# PowerConversion60-12.net
KiCad netlist of a schematic drawn in Altium Designer
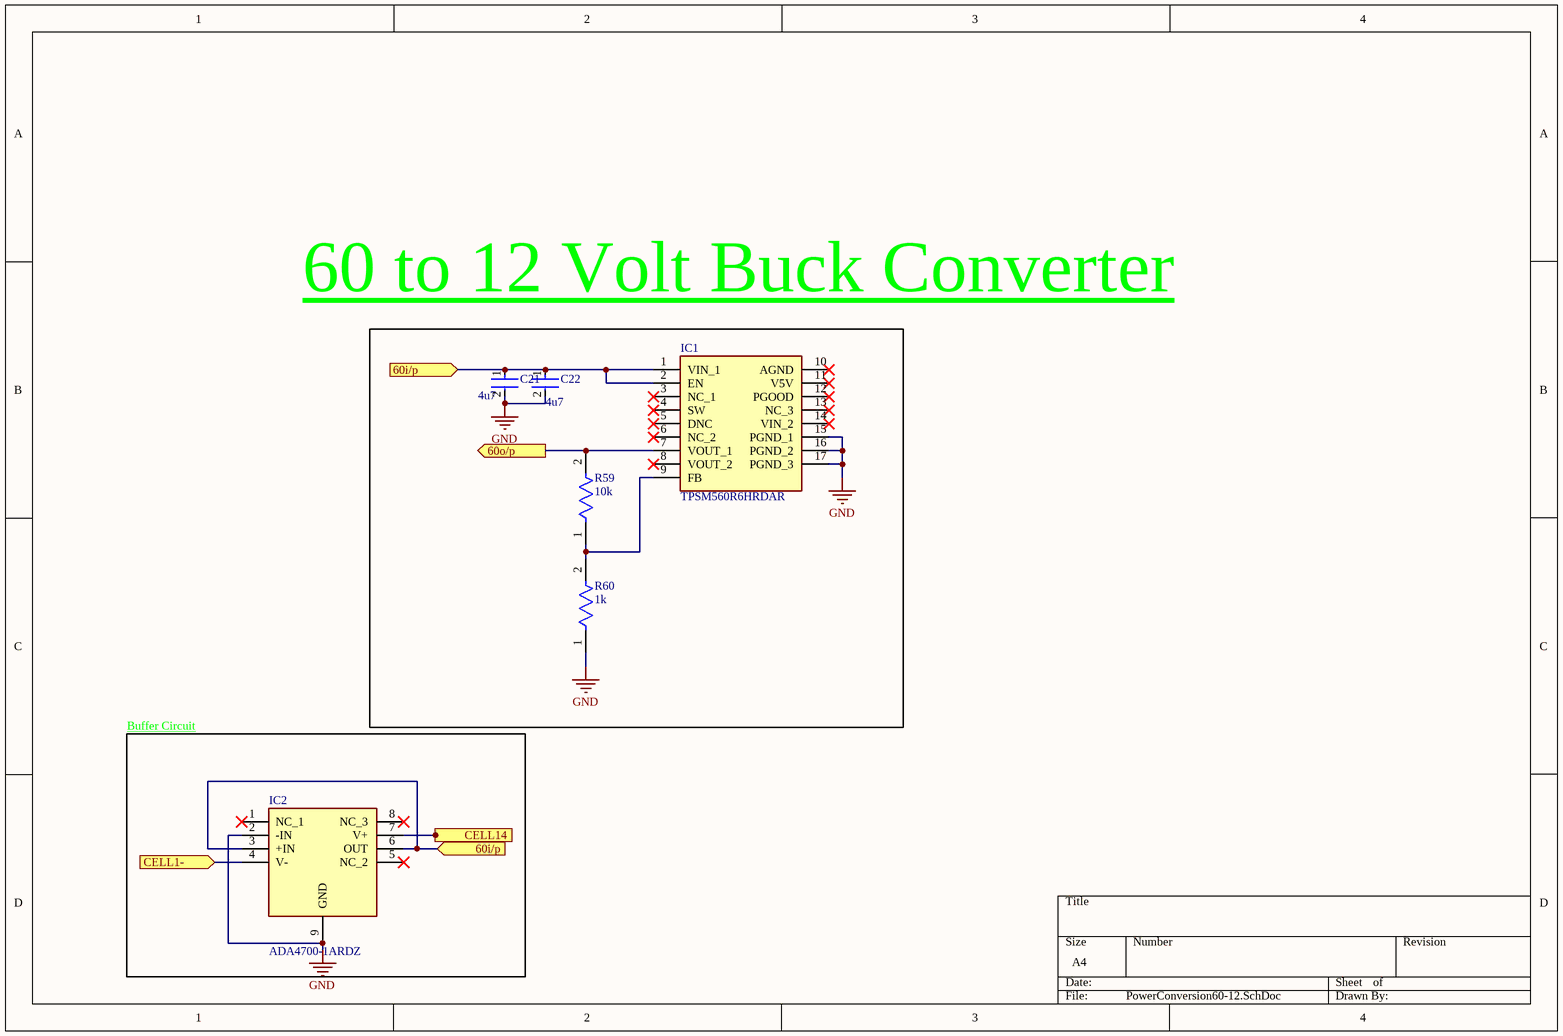
[diagram p0: PowerConversion60-12.SchDoc]

(export (version "E")
  (design (tool "Eeschema 10.0.6"))
  (components
    (comp (ref "C21")
      (value "4u7")
      (footprint "FP-C2012-125-0_2-IPC_B")
      (description "Multilayer Ceramic Capacitors 4.7μF ±10% 50V X5R SMD 0805")
      (fields (field (name "VOLTAGE") "50V") (field (name "TOLERANCE") "10%"))
      (libsource (lib "Altium Content Vault") (part "b4654b650e69147ec39a6b967a45e02"))
    )
    (comp (ref "C22")
      (value "4u7")
      (footprint "FP-C2012-125-0_2-IPC_B")
      (description "Multilayer Ceramic Capacitors 4.7μF ±10% 50V X5R SMD 0805")
      (fields (field (name "VOLTAGE") "50V") (field (name "TOLERANCE") "10%"))
      (libsource (lib "Altium Content Vault") (part "b4654b650e69147ec39a6b967a45e02"))
    )
    (comp (ref "IC1")
      (value "TPSM560R6HRDAR")
      (footprint "SamacSys:TPSM5601R5HEXTRDAR")
      (description "Integrated Circuit")
      (fields (field (name "MOUSER PART NUMBER") "595-TPSM560R6HRDAR"))
      (libsource (lib "*") (part "TPSM560R6HRDAR"))
    )
    (comp (ref "IC2")
      (value "ADA4700-1ARDZ")
      (footprint "SamacSys:SOIC127P600X175-9N")
      (description "Integrated Circuit")
      (fields (field (name "MOUSER PART NUMBER") "584-ADA4700-1ARDZ"))
      (libsource (lib "*") (part "ADA4700-1ARDZ"))
    )
    (comp (ref "R59")
      (value "10k")
      (footprint "FP-RMCF0603-IPC_C")
      (description "10kΩ ±5% 0.1W 0603 Thick Film Chip Resistor AEC-Q200 compliant")
      (fields (field (name "TOLERANCE") "5%"))
      (libsource (lib "Altium Content Vault") (part "1029c3af85768c4190bb7ad29bc67b5"))
    )
    (comp (ref "R60")
      (value "1k")
      (footprint "FP-RC0603-0_55-IPC_C")
      (description "RES 1K OHM 1% 1/10W 0603")
      (fields (field (name "TOLERANCE") "1%"))
      (libsource (lib "Altium Content Vault") (part "1029c3af85768c4190bb7ad29bc67b5"))
    )
  )
  (nets
    (net (code "1") (name "/60i{slash}p") (class "Default")
      (node (ref "C21") (pin "1") (pinfunction "1_1") (pintype "passive"))
      (node (ref "C22") (pin "1") (pinfunction "1_1") (pintype "passive"))
      (node (ref "IC1") (pin "1") (pinfunction "VIN_1_1") (pintype "passive"))
      (node (ref "IC1") (pin "2") (pinfunction "EN_2") (pintype "passive"))
      (node (ref "IC2") (pin "3") (pinfunction "+IN_3") (pintype "passive"))
      (node (ref "IC2") (pin "6") (pinfunction "OUT_6") (pintype "passive"))
    )
    (net (code "2") (name "/60o{slash}p") (class "Default")
      (node (ref "IC1") (pin "7") (pinfunction "VOUT_1_7") (pintype "passive"))
      (node (ref "R59") (pin "2") (pinfunction "2_2") (pintype "passive"))
    )
    (net (code "3") (name "/CELL1-") (class "Default")
      (node (ref "IC2") (pin "4") (pinfunction "V-_4") (pintype "passive"))
    )
    (net (code "4") (name "/CELL14") (class "Default")
      (node (ref "IC2") (pin "7") (pinfunction "V+_7") (pintype "passive"))
    )
    (net (code "5") (name "GND") (class "Default")
      (node (ref "C21") (pin "2") (pinfunction "2_2") (pintype "passive"))
      (node (ref "C22") (pin "2") (pinfunction "2_2") (pintype "passive"))
      (node (ref "IC1") (pin "15") (pinfunction "PGND_1_15") (pintype "passive"))
      (node (ref "IC1") (pin "16") (pinfunction "PGND_2_16") (pintype "passive"))
      (node (ref "IC1") (pin "17") (pinfunction "PGND_3_17") (pintype "passive"))
      (node (ref "IC2") (pin "2") (pinfunction "-IN_2") (pintype "passive"))
      (node (ref "IC2") (pin "9") (pinfunction "GND_9") (pintype "passive"))
      (node (ref "R60") (pin "1") (pinfunction "1_1") (pintype "passive"))
    )
    (net (code "6") (name "Net-(IC1-FB)") (class "Default")
      (node (ref "IC1") (pin "9") (pinfunction "FB_9") (pintype "passive"))
      (node (ref "R59") (pin "1") (pinfunction "1_1") (pintype "passive"))
      (node (ref "R60") (pin "2") (pinfunction "2_2") (pintype "passive"))
    )
    (net (code "7") (name "unconnected-(IC1-AGND-Pad10)") (class "Default")
      (node (ref "IC1") (pin "10") (pinfunction "AGND_10") (pintype "passive+no_connect"))
    )
    (net (code "8") (name "unconnected-(IC1-DNC-Pad5)") (class "Default")
      (node (ref "IC1") (pin "5") (pinfunction "DNC_5") (pintype "passive+no_connect"))
    )
    (net (code "9") (name "unconnected-(IC1-NC_1-Pad3)") (class "Default")
      (node (ref "IC1") (pin "3") (pinfunction "NC_1_3") (pintype "passive+no_connect"))
    )
    (net (code "10") (name "unconnected-(IC1-NC_2-Pad6)") (class "Default")
      (node (ref "IC1") (pin "6") (pinfunction "NC_2_6") (pintype "passive+no_connect"))
    )
    (net (code "11") (name "unconnected-(IC1-NC_3-Pad13)") (class "Default")
      (node (ref "IC1") (pin "13") (pinfunction "NC_3_13") (pintype "passive+no_connect"))
    )
    (net (code "12") (name "unconnected-(IC1-PGOOD-Pad12)") (class "Default")
      (node (ref "IC1") (pin "12") (pinfunction "PGOOD_12") (pintype "passive+no_connect"))
    )
    (net (code "13") (name "unconnected-(IC1-SW-Pad4)") (class "Default")
      (node (ref "IC1") (pin "4") (pinfunction "SW_4") (pintype "passive+no_connect"))
    )
    (net (code "14") (name "unconnected-(IC1-V5V-Pad11)") (class "Default")
      (node (ref "IC1") (pin "11") (pinfunction "V5V_11") (pintype "passive+no_connect"))
    )
    (net (code "15") (name "unconnected-(IC1-VIN_2-Pad14)") (class "Default")
      (node (ref "IC1") (pin "14") (pinfunction "VIN_2_14") (pintype "passive+no_connect"))
    )
    (net (code "16") (name "unconnected-(IC1-VOUT_2-Pad8)") (class "Default")
      (node (ref "IC1") (pin "8") (pinfunction "VOUT_2_8") (pintype "passive+no_connect"))
    )
    (net (code "17") (name "unconnected-(IC2-NC_1-Pad1)") (class "Default")
      (node (ref "IC2") (pin "1") (pinfunction "NC_1_1") (pintype "passive+no_connect"))
    )
    (net (code "18") (name "unconnected-(IC2-NC_2-Pad5)") (class "Default")
      (node (ref "IC2") (pin "5") (pinfunction "NC_2_5") (pintype "passive+no_connect"))
    )
    (net (code "19") (name "unconnected-(IC2-NC_3-Pad8)") (class "Default")
      (node (ref "IC2") (pin "8") (pinfunction "NC_3_8") (pintype "passive+no_connect"))
    )
  )
)
